# untitled.net
KiCad netlist of a schematic drawn in EAGLE
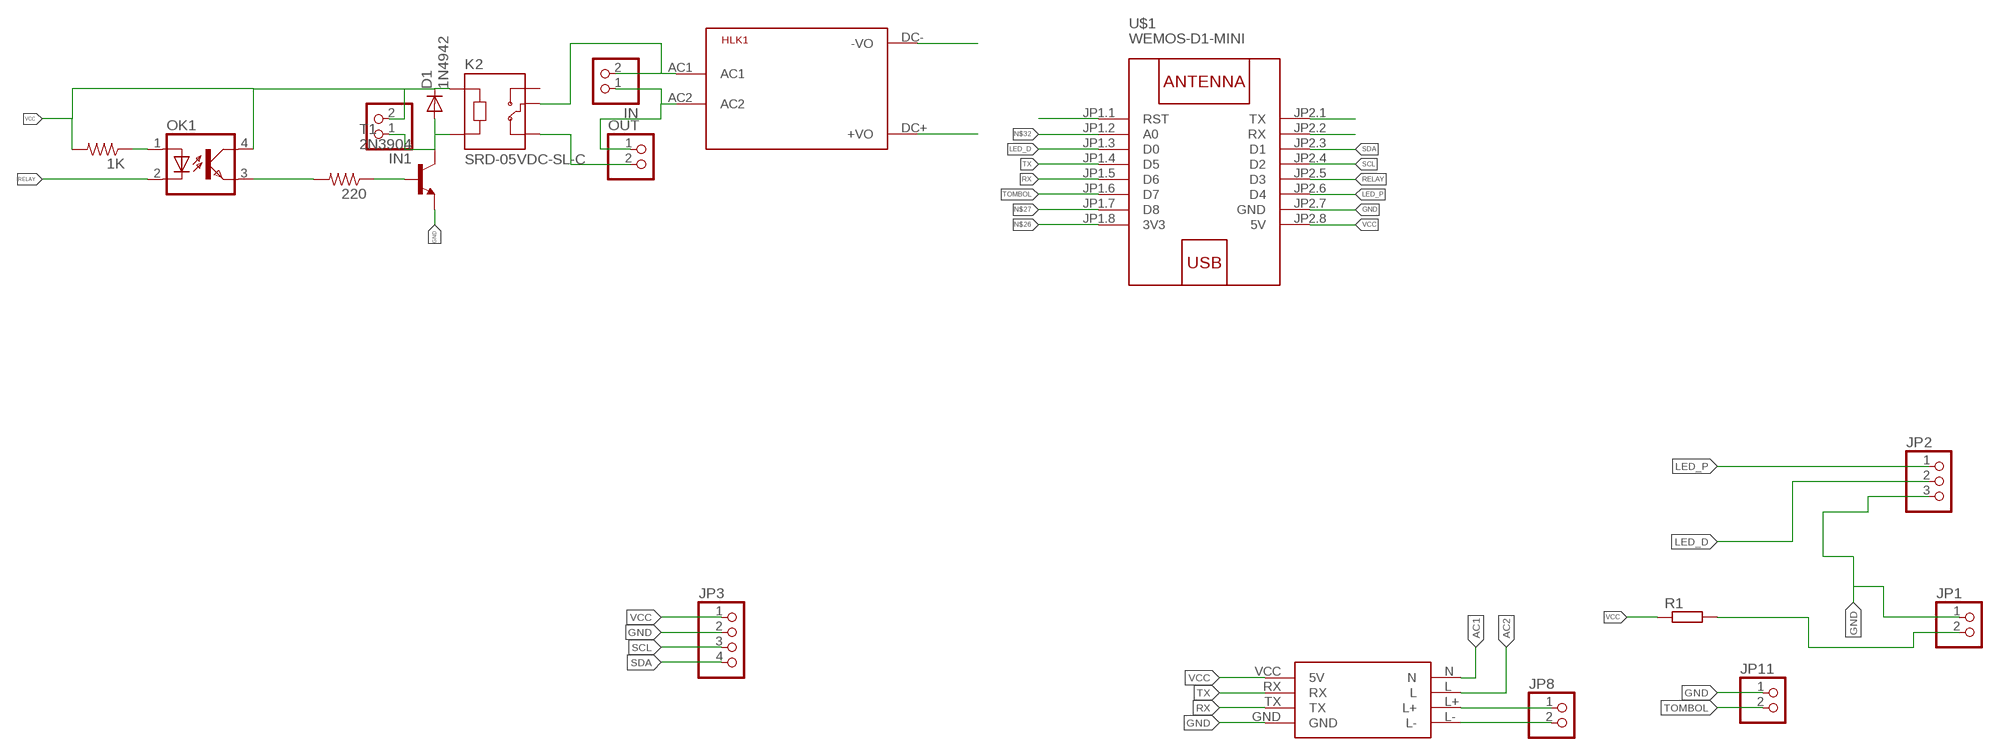
[diagram p0: schematic, sheet 1]

(export (version "E")
  (design (tool "Eeschema 10.0.6"))
  (components
    (comp (ref "1K")
      (value "R-US_0204/7")
      (footprint "eagle-import:0204_7")
      (libsource (lib "eagle-import") (part "R-US_0204/7"))
    )
    (comp (ref "220")
      (value "R-US_0204/7")
      (footprint "eagle-import:0204_7")
      (libsource (lib "eagle-import") (part "R-US_0204/7"))
    )
    (comp (ref "D1")
      (value "1N4942")
      (footprint "eagle-import:DO41-10")
      (libsource (lib "eagle-import") (part "1N4942"))
    )
    (comp (ref "HLK1")
      (value "HLK-PM013W")
      (footprint "eagle-import:HLK-PM01")
      (libsource (lib "eagle-import") (part "HLK-PM013W"))
    )
    (comp (ref "IN")
      (value "PINHD-1X2")
      (footprint "eagle-import:1X02")
      (libsource (lib "eagle-import") (part "PINHD-1X2"))
    )
    (comp (ref "IN1")
      (value "PINHD-1X2")
      (footprint "eagle-import:1X02")
      (libsource (lib "eagle-import") (part "PINHD-1X2"))
    )
    (comp (ref "JP1")
      (value "PINHD-1X2")
      (footprint "eagle-import:1X02")
      (libsource (lib "eagle-import") (part "PINHD-1X2"))
    )
    (comp (ref "JP2")
      (value "PINHD-1X3")
      (footprint "eagle-import:1X03")
      (libsource (lib "eagle-import") (part "PINHD-1X3"))
    )
    (comp (ref "JP3")
      (value "PINHD-1X4")
      (footprint "eagle-import:1X04")
      (libsource (lib "eagle-import") (part "PINHD-1X4"))
    )
    (comp (ref "JP8")
      (value "PINHD-1X2")
      (footprint "eagle-import:1X02")
      (libsource (lib "eagle-import") (part "PINHD-1X2"))
    )
    (comp (ref "JP11")
      (value "PINHD-1X2")
      (footprint "eagle-import:1X02")
      (libsource (lib "eagle-import") (part "PINHD-1X2"))
    )
    (comp (ref "K2")
      (value "SRD-05VDC-SL-C")
      (footprint "eagle-import:RELAY_SRD-05VDC-SL-C")
      (fields (field (name "MF") "Songle Relay"))
      (libsource (lib "eagle-import") (part "SRD-05VDC-SL-C"))
    )
    (comp (ref "OK1")
      (value "PC817")
      (footprint "eagle-import:DIL04")
      (libsource (lib "eagle-import") (part "PC817"))
    )
    (comp (ref "OUT")
      (value "PINHD-1X2")
      (footprint "eagle-import:1X02")
      (libsource (lib "eagle-import") (part "PINHD-1X2"))
    )
    (comp (ref "R1")
      (value "R-EU_0204/7")
      (footprint "eagle-import:0204_7")
      (libsource (lib "eagle-import") (part "R-EU_0204/7"))
    )
    (comp (ref "T1")
      (value "2N3904")
      (footprint "eagle-import:TO92")
      (libsource (lib "eagle-import") (part "2N3904"))
    )
    (comp (ref "U$1")
      (value "WEMOS-D1-MINI")
      (footprint "eagle-import:WEMOS-D1-MINI")
      (libsource (lib "eagle-import") (part "WEMOS-D1-MINI"))
    )
    (comp (ref "U$2")
      (value "PZEM004T")
      (footprint "eagle-import:PZEM004T")
      (libsource (lib "eagle-import") (part "PZEM004T"))
    )
  )
  (nets
    (net (code "1") (name "AC1") (class "Default")
      (node (ref "HLK1") (pin "AC1") (pinfunction "AC1_AC1") (pintype "bidirectional"))
      (node (ref "IN") (pin "2") (pinfunction "2_2") (pintype "passive"))
      (node (ref "K2") (pin "COM") (pinfunction "COM_COM") (pintype "passive"))
      (node (ref "U$2") (pin "N") (pinfunction "N_N") (pintype "bidirectional"))
    )
    (net (code "2") (name "AC2") (class "Default")
      (node (ref "HLK1") (pin "AC2") (pinfunction "AC2_AC2") (pintype "bidirectional"))
      (node (ref "IN") (pin "1") (pinfunction "1_1") (pintype "passive"))
      (node (ref "OUT") (pin "1") (pinfunction "1_1") (pintype "passive"))
      (node (ref "U$2") (pin "L") (pinfunction "L_L") (pintype "bidirectional"))
    )
    (net (code "3") (name "GND") (class "Default")
      (node (ref "HLK1") (pin "DC-") (pinfunction "-VO_DC-") (pintype "bidirectional"))
      (node (ref "JP1") (pin "1") (pinfunction "1_1") (pintype "passive"))
      (node (ref "JP11") (pin "1") (pinfunction "1_1") (pintype "passive"))
      (node (ref "JP2") (pin "3") (pinfunction "3_3") (pintype "passive"))
      (node (ref "JP3") (pin "2") (pinfunction "2_2") (pintype "passive"))
      (node (ref "T1") (pin "3") (pinfunction "E_3") (pintype "passive"))
      (node (ref "U$1") (pin "JP2.7") (pinfunction "GND_JP2.7") (pintype "power_in"))
      (node (ref "U$2") (pin "GND") (pinfunction "GND_GND") (pintype "bidirectional"))
    )
    (net (code "4") (name "LED_D") (class "Default")
      (node (ref "JP2") (pin "2") (pinfunction "2_2") (pintype "passive"))
      (node (ref "U$1") (pin "JP1.3") (pinfunction "D0_JP1.3") (pintype "bidirectional"))
    )
    (net (code "5") (name "LED_P") (class "Default")
      (node (ref "JP2") (pin "1") (pinfunction "1_1") (pintype "passive"))
      (node (ref "U$1") (pin "JP2.6") (pinfunction "D4_JP2.6") (pintype "bidirectional"))
    )
    (net (code "6") (name "N$26") (class "Default")
      (node (ref "U$1") (pin "JP1.8") (pinfunction "3V3_JP1.8") (pintype "power_in"))
    )
    (net (code "7") (name "N$27") (class "Default")
      (node (ref "U$1") (pin "JP1.7") (pinfunction "D8_JP1.7") (pintype "bidirectional"))
    )
    (net (code "8") (name "N$32") (class "Default")
      (node (ref "U$1") (pin "JP1.2") (pinfunction "A0_JP1.2") (pintype "bidirectional"))
    )
    (net (code "9") (name "Net-(JP1-Pad2)") (class "Default")
      (node (ref "JP1") (pin "2") (pinfunction "2_2") (pintype "passive"))
      (node (ref "R1") (pin "2") (pinfunction "2_2") (pintype "passive"))
    )
    (net (code "10") (name "Net-(JP8-Pad1)") (class "Default")
      (node (ref "JP8") (pin "1") (pinfunction "1_1") (pintype "passive"))
      (node (ref "U$2") (pin "L+") (pinfunction "L+_L+") (pintype "bidirectional"))
    )
    (net (code "11") (name "Net-(JP8-Pad2)") (class "Default")
      (node (ref "JP8") (pin "2") (pinfunction "2_2") (pintype "passive"))
      (node (ref "U$2") (pin "L-") (pinfunction "L-_L-") (pintype "bidirectional"))
    )
    (net (code "12") (name "Net-(K2-PadNC)") (class "Default")
      (node (ref "K2") (pin "NC") (pinfunction "NC_NC") (pintype "passive"))
      (node (ref "OUT") (pin "2") (pinfunction "2_2") (pintype "passive"))
    )
    (net (code "13") (name "Net-(OK1-A)") (class "Default")
      (node (ref "1K") (pin "1") (pinfunction "1_1") (pintype "passive"))
      (node (ref "OK1") (pin "1") (pinfunction "A_1") (pintype "passive"))
    )
    (net (code "14") (name "Net-(OK1-EMIT)") (class "Default")
      (node (ref "220") (pin "2") (pinfunction "2_2") (pintype "passive"))
      (node (ref "OK1") (pin "3") (pinfunction "EMIT_3") (pintype "passive"))
    )
    (net (code "15") (name "Net-(T1-B)") (class "Default")
      (node (ref "220") (pin "1") (pinfunction "1_1") (pintype "passive"))
      (node (ref "T1") (pin "2") (pinfunction "B_2") (pintype "passive"))
    )
    (net (code "16") (name "Net-(T1-C)") (class "Default")
      (node (ref "D1") (pin "A") (pinfunction "A_A") (pintype "passive"))
      (node (ref "IN1") (pin "1") (pinfunction "1_1") (pintype "passive"))
      (node (ref "K2") (pin "A2") (pinfunction "A2_A2") (pintype "passive"))
      (node (ref "T1") (pin "1") (pinfunction "C_1") (pintype "passive"))
    )
    (net (code "17") (name "RELAY") (class "Default")
      (node (ref "OK1") (pin "2") (pinfunction "C_2") (pintype "passive"))
      (node (ref "U$1") (pin "JP2.5") (pinfunction "D3_JP2.5") (pintype "bidirectional"))
    )
    (net (code "18") (name "RX") (class "Default")
      (node (ref "U$1") (pin "JP1.5") (pinfunction "D6_JP1.5") (pintype "bidirectional"))
      (node (ref "U$2") (pin "TX") (pinfunction "TX_TX") (pintype "bidirectional"))
    )
    (net (code "19") (name "SCL") (class "Default")
      (node (ref "JP3") (pin "3") (pinfunction "3_3") (pintype "passive"))
      (node (ref "U$1") (pin "JP2.4") (pinfunction "D2_JP2.4") (pintype "bidirectional"))
    )
    (net (code "20") (name "SDA") (class "Default")
      (node (ref "JP3") (pin "4") (pinfunction "4_4") (pintype "passive"))
      (node (ref "U$1") (pin "JP2.3") (pinfunction "D1_JP2.3") (pintype "bidirectional"))
    )
    (net (code "21") (name "TOMBOL") (class "Default")
      (node (ref "JP11") (pin "2") (pinfunction "2_2") (pintype "passive"))
      (node (ref "U$1") (pin "JP1.6") (pinfunction "D7_JP1.6") (pintype "bidirectional"))
    )
    (net (code "22") (name "TX") (class "Default")
      (node (ref "U$1") (pin "JP1.4") (pinfunction "D5_JP1.4") (pintype "bidirectional"))
      (node (ref "U$2") (pin "RX") (pinfunction "RX_RX") (pintype "bidirectional"))
    )
    (net (code "23") (name "VCC") (class "Default")
      (node (ref "1K") (pin "2") (pinfunction "2_2") (pintype "passive"))
      (node (ref "D1") (pin "C") (pinfunction "C_C") (pintype "passive"))
      (node (ref "HLK1") (pin "DC+") (pinfunction "+VO_DC+") (pintype "bidirectional"))
      (node (ref "IN1") (pin "2") (pinfunction "2_2") (pintype "passive"))
      (node (ref "JP3") (pin "1") (pinfunction "1_1") (pintype "passive"))
      (node (ref "K2") (pin "A1") (pinfunction "A1_A1") (pintype "passive"))
      (node (ref "OK1") (pin "4") (pinfunction "COL_4") (pintype "passive"))
      (node (ref "R1") (pin "1") (pinfunction "1_1") (pintype "passive"))
      (node (ref "U$1") (pin "JP2.8") (pinfunction "5V_JP2.8") (pintype "power_in"))
      (node (ref "U$2") (pin "VCC") (pinfunction "5V_VCC") (pintype "bidirectional"))
    )
    (net (code "24") (name "unconnected-(K2-PadNO)") (class "Default")
      (node (ref "K2") (pin "NO") (pinfunction "NO_NO") (pintype "passive"))
    )
    (net (code "25") (name "unconnected-(U$1-RST-PadJP1.1)") (class "Default")
      (node (ref "U$1") (pin "JP1.1") (pinfunction "RST_JP1.1") (pintype "bidirectional"))
    )
    (net (code "26") (name "unconnected-(U$1-RX-PadJP2.2)") (class "Default")
      (node (ref "U$1") (pin "JP2.2") (pinfunction "RX_JP2.2") (pintype "bidirectional"))
    )
    (net (code "27") (name "unconnected-(U$1-TX-PadJP2.1)") (class "Default")
      (node (ref "U$1") (pin "JP2.1") (pinfunction "TX_JP2.1") (pintype "bidirectional"))
    )
  )
)
